# GPS.net
KiCad netlist of a schematic drawn in EAGLE
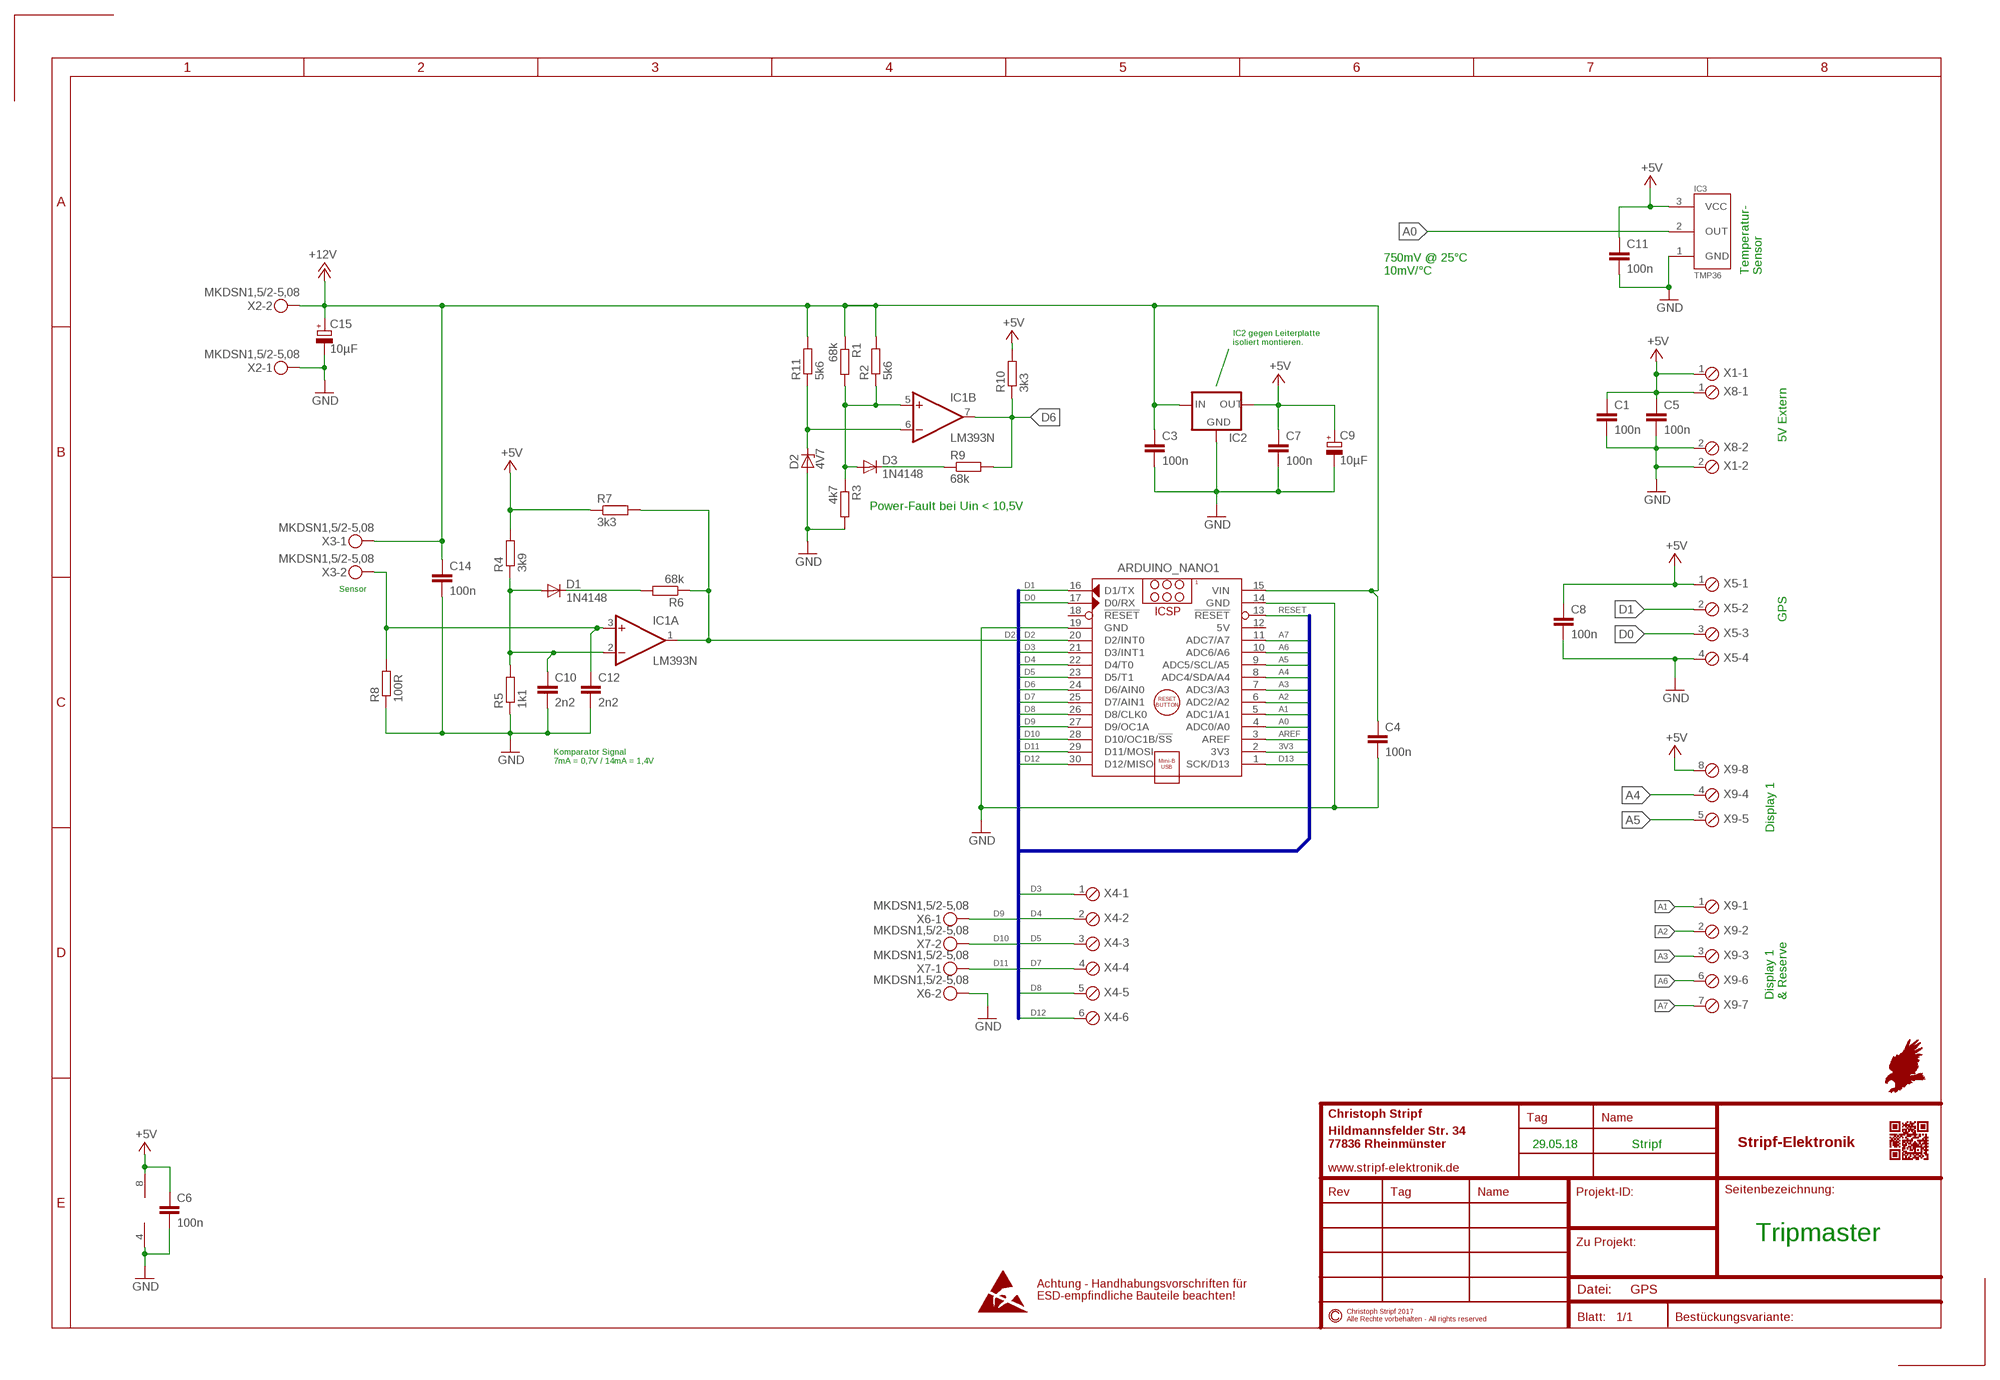
[diagram p0: schematic, sheet 1]

(export (version "E")
  (design (tool "Eeschema 10.0.6"))
  (components
    (comp (ref "ARDUINO_NANO1")
      (value "ARDUINO_NANO")
      (footprint "eagle-import:ARDUINO_NANO")
      (libsource (lib "eagle-import") (part "ARDUINO_NANO"))
    )
    (comp (ref "C1")
      (value "100n")
      (footprint "eagle-import:C025-030X050")
      (libsource (lib "eagle-import") (part "C-EU025-030X050"))
    )
    (comp (ref "C3")
      (value "100n")
      (footprint "eagle-import:C025-030X050")
      (libsource (lib "eagle-import") (part "C-EU025-030X050"))
    )
    (comp (ref "C4")
      (value "100n")
      (footprint "eagle-import:C025-030X050")
      (libsource (lib "eagle-import") (part "C-EU025-030X050"))
    )
    (comp (ref "C5")
      (value "100n")
      (footprint "eagle-import:C025-030X050")
      (libsource (lib "eagle-import") (part "C-EU025-030X050"))
    )
    (comp (ref "C6")
      (value "100n")
      (footprint "eagle-import:C025-030X050")
      (libsource (lib "eagle-import") (part "C-EU025-030X050"))
    )
    (comp (ref "C7")
      (value "100n")
      (footprint "eagle-import:C025-030X050")
      (libsource (lib "eagle-import") (part "C-EU025-030X050"))
    )
    (comp (ref "C8")
      (value "100n")
      (footprint "eagle-import:C025-030X050")
      (libsource (lib "eagle-import") (part "C-EU025-030X050"))
    )
    (comp (ref "C9")
      (value "10µF")
      (footprint "eagle-import:E2,5-6")
      (libsource (lib "eagle-import") (part "CPOL-EUE2.5-6"))
    )
    (comp (ref "C10")
      (value "2n2")
      (footprint "eagle-import:C025-030X050")
      (libsource (lib "eagle-import") (part "C-EU025-030X050"))
    )
    (comp (ref "C11")
      (value "100n")
      (footprint "eagle-import:C025-030X050")
      (libsource (lib "eagle-import") (part "C-EU025-030X050"))
    )
    (comp (ref "C12")
      (value "2n2")
      (footprint "eagle-import:C025-030X050")
      (libsource (lib "eagle-import") (part "C-EU025-030X050"))
    )
    (comp (ref "C14")
      (value "100n")
      (footprint "eagle-import:C025-030X050")
      (libsource (lib "eagle-import") (part "C-EU025-030X050"))
    )
    (comp (ref "C15")
      (value "10µF")
      (footprint "eagle-import:E2,5-6")
      (libsource (lib "eagle-import") (part "CPOL-EUE2.5-6"))
    )
    (comp (ref "D1")
      (value "1N4148")
      (footprint "eagle-import:DO35-7")
      (libsource (lib "eagle-import") (part "1N4148DO35-7"))
    )
    (comp (ref "D2")
      (value "4V7")
      (footprint "eagle-import:ZDIO-2.5")
      (libsource (lib "eagle-import") (part "ZENER-DIODEZD-2.5"))
    )
    (comp (ref "D3")
      (value "1N4148")
      (footprint "eagle-import:DO35-7")
      (libsource (lib "eagle-import") (part "1N4148DO35-7"))
    )
    (comp (ref "IC1")
      (value "LM393N")
      (footprint "eagle-import:DIL08")
      (libsource (lib "eagle-import") (part "LM393N"))
    )
    (comp (ref "IC2")
      (value "78XXL")
      (footprint "eagle-import:78XXL")
      (libsource (lib "eagle-import") (part "78XXL"))
    )
    (comp (ref "IC3")
      (value "TMP36")
      (footprint "eagle-import:TO92-LINE")
      (libsource (lib "eagle-import") (part "TMP36"))
    )
    (comp (ref "R1")
      (value "68k")
      (footprint "eagle-import:0207_2V")
      (libsource (lib "eagle-import") (part "R-EU_0207/2V"))
    )
    (comp (ref "R2")
      (value "5k6")
      (footprint "eagle-import:0207_2V")
      (libsource (lib "eagle-import") (part "R-EU_0207/2V"))
    )
    (comp (ref "R3")
      (value "4k7")
      (footprint "eagle-import:0207_2V")
      (libsource (lib "eagle-import") (part "R-EU_0207/2V"))
    )
    (comp (ref "R4")
      (value "3k9")
      (footprint "eagle-import:0207_2V")
      (libsource (lib "eagle-import") (part "R-EU_0207/2V"))
    )
    (comp (ref "R5")
      (value "1k1")
      (footprint "eagle-import:0207_2V")
      (libsource (lib "eagle-import") (part "R-EU_0207/2V"))
    )
    (comp (ref "R6")
      (value "68k")
      (footprint "eagle-import:0207_2V")
      (libsource (lib "eagle-import") (part "R-EU_0207/2V"))
    )
    (comp (ref "R7")
      (value "3k3")
      (footprint "eagle-import:0207_2V")
      (libsource (lib "eagle-import") (part "R-EU_0207/2V"))
    )
    (comp (ref "R8")
      (value "100R")
      (footprint "eagle-import:0207_2V")
      (libsource (lib "eagle-import") (part "R-EU_0207/2V"))
    )
    (comp (ref "R9")
      (value "68k")
      (footprint "eagle-import:0207_2V")
      (libsource (lib "eagle-import") (part "R-EU_0207/2V"))
    )
    (comp (ref "R10")
      (value "3k3")
      (footprint "eagle-import:0207_2V")
      (libsource (lib "eagle-import") (part "R-EU_0207/2V"))
    )
    (comp (ref "R11")
      (value "5k6")
      (footprint "eagle-import:0207_2V")
      (libsource (lib "eagle-import") (part "R-EU_0207/2V"))
    )
    (comp (ref "X1")
      (value "MPT2")
      (footprint "eagle-import:2POL254")
      (libsource (lib "eagle-import") (part "MPT2"))
    )
    (comp (ref "X2")
      (value "MKDSN1,5/2-5,08")
      (footprint "eagle-import:MKDSN1,5_2-5,08")
      (libsource (lib "eagle-import") (part "MKDSN1,5/2-5,08"))
    )
    (comp (ref "X3")
      (value "MKDSN1,5/2-5,08")
      (footprint "eagle-import:MKDSN1,5_2-5,08")
      (libsource (lib "eagle-import") (part "MKDSN1,5/2-5,08"))
    )
    (comp (ref "X4")
      (value "MPT6")
      (footprint "eagle-import:6POL254")
      (libsource (lib "eagle-import") (part "MPT6"))
    )
    (comp (ref "X5")
      (value "MPT4")
      (footprint "eagle-import:4POL254")
      (libsource (lib "eagle-import") (part "MPT4"))
    )
    (comp (ref "X6")
      (value "MKDSN1,5/2-5,08")
      (footprint "eagle-import:MKDSN1,5_2-5,08")
      (libsource (lib "eagle-import") (part "MKDSN1,5/2-5,08"))
    )
    (comp (ref "X7")
      (value "MKDSN1,5/2-5,08")
      (footprint "eagle-import:MKDSN1,5_2-5,08")
      (libsource (lib "eagle-import") (part "MKDSN1,5/2-5,08"))
    )
    (comp (ref "X8")
      (value "MPT2")
      (footprint "eagle-import:2POL254")
      (libsource (lib "eagle-import") (part "MPT2"))
    )
    (comp (ref "X9")
      (value "MPT8")
      (footprint "eagle-import:8POL254")
      (libsource (lib "eagle-import") (part "MPT8"))
    )
  )
  (nets
    (net (code "1") (name "+5V") (class "Default")
      (node (ref "C1") (pin "1") (pinfunction "1_1") (pintype "passive"))
      (node (ref "C11") (pin "1") (pinfunction "1_1") (pintype "passive"))
      (node (ref "C5") (pin "1") (pinfunction "1_1") (pintype "passive"))
      (node (ref "C6") (pin "1") (pinfunction "1_1") (pintype "passive"))
      (node (ref "C7") (pin "1") (pinfunction "1_1") (pintype "passive"))
      (node (ref "C8") (pin "1") (pinfunction "1_1") (pintype "passive"))
      (node (ref "C9") (pin "+") (pinfunction "+_+") (pintype "passive"))
      (node (ref "IC1") (pin "8") (pinfunction "V+_8") (pintype "power_in"))
      (node (ref "IC2") (pin "OUT") (pinfunction "OUT_OUT") (pintype "passive"))
      (node (ref "IC3") (pin "3") (pinfunction "VCC_3") (pintype "bidirectional"))
      (node (ref "R10") (pin "2") (pinfunction "2_2") (pintype "passive"))
      (node (ref "R4") (pin "2") (pinfunction "2_2") (pintype "passive"))
      (node (ref "R7") (pin "1") (pinfunction "1_1") (pintype "passive"))
      (node (ref "X1") (pin "1") (pinfunction "1_1") (pintype "passive"))
      (node (ref "X5") (pin "1") (pinfunction "1_1") (pintype "passive"))
      (node (ref "X8") (pin "1") (pinfunction "1_1") (pintype "passive"))
      (node (ref "X9") (pin "8") (pinfunction "1_8") (pintype "passive"))
    )
    (net (code "2") (name "+12V") (class "Default")
      (node (ref "ARDUINO_NANO1") (pin "15") (pinfunction "VIN_15") (pintype "power_in"))
      (node (ref "C14") (pin "1") (pinfunction "1_1") (pintype "passive"))
      (node (ref "C15") (pin "+") (pinfunction "+_+") (pintype "passive"))
      (node (ref "C3") (pin "1") (pinfunction "1_1") (pintype "passive"))
      (node (ref "C4") (pin "1") (pinfunction "1_1") (pintype "passive"))
      (node (ref "IC2") (pin "IN") (pinfunction "IN_IN") (pintype "input"))
      (node (ref "R1") (pin "1") (pinfunction "1_1") (pintype "passive"))
      (node (ref "R11") (pin "2") (pinfunction "2_2") (pintype "passive"))
      (node (ref "R2") (pin "2") (pinfunction "2_2") (pintype "passive"))
      (node (ref "X2") (pin "2") (pinfunction "KL_2") (pintype "passive"))
      (node (ref "X3") (pin "1") (pinfunction "KL_1") (pintype "passive"))
    )
    (net (code "3") (name "/3V3") (class "Default")
      (node (ref "ARDUINO_NANO1") (pin "2") (pinfunction "3V3_2") (pintype "output"))
    )
    (net (code "4") (name "/5V") (class "Default")
      (node (ref "ARDUINO_NANO1") (pin "12") (pinfunction "5V_12") (pintype "power_in"))
    )
    (net (code "5") (name "/AREF") (class "Default")
      (node (ref "ARDUINO_NANO1") (pin "3") (pinfunction "AREF_3") (pintype "input"))
    )
    (net (code "6") (name "/D2") (class "Default")
      (node (ref "ARDUINO_NANO1") (pin "20") (pinfunction "D2/INT0_20") (pintype "bidirectional"))
      (node (ref "IC1") (pin "1") (pinfunction "OUT_1") (pintype "output"))
      (node (ref "R6") (pin "1") (pinfunction "1_1") (pintype "passive"))
      (node (ref "R7") (pin "2") (pinfunction "2_2") (pintype "passive"))
    )
    (net (code "7") (name "/D3") (class "Default")
      (node (ref "ARDUINO_NANO1") (pin "21") (pinfunction "D3/INT1_21") (pintype "bidirectional"))
      (node (ref "X4") (pin "1") (pinfunction "1_1") (pintype "passive"))
    )
    (net (code "8") (name "/D4") (class "Default")
      (node (ref "ARDUINO_NANO1") (pin "22") (pinfunction "D4/T0_22") (pintype "bidirectional"))
      (node (ref "X4") (pin "2") (pinfunction "1_2") (pintype "passive"))
    )
    (net (code "9") (name "/D5") (class "Default")
      (node (ref "ARDUINO_NANO1") (pin "23") (pinfunction "D5/T1_23") (pintype "bidirectional"))
      (node (ref "X4") (pin "3") (pinfunction "1_3") (pintype "passive"))
    )
    (net (code "10") (name "/D7") (class "Default")
      (node (ref "ARDUINO_NANO1") (pin "25") (pinfunction "D7/AIN1_25") (pintype "bidirectional"))
      (node (ref "X4") (pin "4") (pinfunction "1_4") (pintype "passive"))
    )
    (net (code "11") (name "/D8") (class "Default")
      (node (ref "ARDUINO_NANO1") (pin "26") (pinfunction "D8/CLK0_26") (pintype "bidirectional"))
      (node (ref "X4") (pin "5") (pinfunction "1_5") (pintype "passive"))
    )
    (net (code "12") (name "/D9") (class "Default")
      (node (ref "ARDUINO_NANO1") (pin "27") (pinfunction "D9/OC1A_27") (pintype "bidirectional"))
      (node (ref "X6") (pin "1") (pinfunction "KL_1") (pintype "passive"))
    )
    (net (code "13") (name "/D10") (class "Default")
      (node (ref "ARDUINO_NANO1") (pin "28") (pinfunction "D10/OC1B/~{SS}_28") (pintype "bidirectional"))
      (node (ref "X7") (pin "2") (pinfunction "KL_2") (pintype "passive"))
    )
    (net (code "14") (name "/D11") (class "Default")
      (node (ref "ARDUINO_NANO1") (pin "29") (pinfunction "D11/MOSI_29") (pintype "bidirectional"))
      (node (ref "X7") (pin "1") (pinfunction "KL_1") (pintype "passive"))
    )
    (net (code "15") (name "/D12") (class "Default")
      (node (ref "ARDUINO_NANO1") (pin "30") (pinfunction "D12/MISO_30") (pintype "bidirectional"))
      (node (ref "X4") (pin "6") (pinfunction "1_6") (pintype "passive"))
    )
    (net (code "16") (name "/D13") (class "Default")
      (node (ref "ARDUINO_NANO1") (pin "1") (pinfunction "SCK/D13_1") (pintype "bidirectional"))
    )
    (net (code "17") (name "/RESET") (class "Default")
      (node (ref "ARDUINO_NANO1") (pin "13") (pinfunction "~{RESET}_13") (pintype "input"))
    )
    (net (code "18") (name "A0") (class "Default")
      (node (ref "ARDUINO_NANO1") (pin "4") (pinfunction "ADC0/A0_4") (pintype "bidirectional"))
      (node (ref "IC3") (pin "2") (pinfunction "OUT_2") (pintype "bidirectional"))
    )
    (net (code "19") (name "A1") (class "Default")
      (node (ref "ARDUINO_NANO1") (pin "5") (pinfunction "ADC1/A1_5") (pintype "bidirectional"))
      (node (ref "X9") (pin "1") (pinfunction "1_1") (pintype "passive"))
    )
    (net (code "20") (name "A2") (class "Default")
      (node (ref "ARDUINO_NANO1") (pin "6") (pinfunction "ADC2/A2_6") (pintype "bidirectional"))
      (node (ref "X9") (pin "2") (pinfunction "1_2") (pintype "passive"))
    )
    (net (code "21") (name "A3") (class "Default")
      (node (ref "ARDUINO_NANO1") (pin "7") (pinfunction "ADC3/A3_7") (pintype "bidirectional"))
      (node (ref "X9") (pin "3") (pinfunction "1_3") (pintype "passive"))
    )
    (net (code "22") (name "A4") (class "Default")
      (node (ref "ARDUINO_NANO1") (pin "8") (pinfunction "ADC4/SDA/A4_8") (pintype "bidirectional"))
      (node (ref "X9") (pin "4") (pinfunction "1_4") (pintype "passive"))
    )
    (net (code "23") (name "A5") (class "Default")
      (node (ref "ARDUINO_NANO1") (pin "9") (pinfunction "ADC5/SCL/A5_9") (pintype "bidirectional"))
      (node (ref "X9") (pin "5") (pinfunction "1_5") (pintype "passive"))
    )
    (net (code "24") (name "A6") (class "Default")
      (node (ref "ARDUINO_NANO1") (pin "10") (pinfunction "ADC6/A6_10") (pintype "bidirectional"))
      (node (ref "X9") (pin "6") (pinfunction "1_6") (pintype "passive"))
    )
    (net (code "25") (name "A7") (class "Default")
      (node (ref "ARDUINO_NANO1") (pin "11") (pinfunction "ADC7/A7_11") (pintype "bidirectional"))
      (node (ref "X9") (pin "7") (pinfunction "1_7") (pintype "passive"))
    )
    (net (code "26") (name "D0") (class "Default")
      (node (ref "ARDUINO_NANO1") (pin "17") (pinfunction "D0/RX_17") (pintype "bidirectional"))
      (node (ref "X5") (pin "3") (pinfunction "1_3") (pintype "passive"))
    )
    (net (code "27") (name "D1") (class "Default")
      (node (ref "ARDUINO_NANO1") (pin "16") (pinfunction "D1/TX_16") (pintype "bidirectional"))
      (node (ref "X5") (pin "2") (pinfunction "1_2") (pintype "passive"))
    )
    (net (code "28") (name "D6") (class "Default")
      (node (ref "ARDUINO_NANO1") (pin "24") (pinfunction "D6/AIN0_24") (pintype "bidirectional"))
      (node (ref "IC1") (pin "7") (pinfunction "OUT_7") (pintype "output"))
      (node (ref "R10") (pin "1") (pinfunction "1_1") (pintype "passive"))
      (node (ref "R9") (pin "2") (pinfunction "2_2") (pintype "passive"))
    )
    (net (code "29") (name "GND") (class "Default")
      (node (ref "ARDUINO_NANO1") (pin "14") (pinfunction "GND_14") (pintype "power_in"))
      (node (ref "ARDUINO_NANO1") (pin "19") (pinfunction "GND_19") (pintype "power_in"))
      (node (ref "C1") (pin "2") (pinfunction "2_2") (pintype "passive"))
      (node (ref "C10") (pin "2") (pinfunction "2_2") (pintype "passive"))
      (node (ref "C11") (pin "2") (pinfunction "2_2") (pintype "passive"))
      (node (ref "C12") (pin "2") (pinfunction "2_2") (pintype "passive"))
      (node (ref "C14") (pin "2") (pinfunction "2_2") (pintype "passive"))
      (node (ref "C15") (pin "-") (pinfunction "-_-") (pintype "passive"))
      (node (ref "C3") (pin "2") (pinfunction "2_2") (pintype "passive"))
      (node (ref "C4") (pin "2") (pinfunction "2_2") (pintype "passive"))
      (node (ref "C5") (pin "2") (pinfunction "2_2") (pintype "passive"))
      (node (ref "C6") (pin "2") (pinfunction "2_2") (pintype "passive"))
      (node (ref "C7") (pin "2") (pinfunction "2_2") (pintype "passive"))
      (node (ref "C8") (pin "2") (pinfunction "2_2") (pintype "passive"))
      (node (ref "C9") (pin "-") (pinfunction "-_-") (pintype "passive"))
      (node (ref "D2") (pin "A") (pinfunction "A_A") (pintype "passive"))
      (node (ref "IC1") (pin "4") (pinfunction "V-_4") (pintype "power_in"))
      (node (ref "IC2") (pin "GND") (pinfunction "GND_GND") (pintype "input"))
      (node (ref "IC3") (pin "1") (pinfunction "GND_1") (pintype "bidirectional"))
      (node (ref "R3") (pin "2") (pinfunction "2_2") (pintype "passive"))
      (node (ref "R5") (pin "1") (pinfunction "1_1") (pintype "passive"))
      (node (ref "R8") (pin "1") (pinfunction "1_1") (pintype "passive"))
      (node (ref "X1") (pin "2") (pinfunction "1_2") (pintype "passive"))
      (node (ref "X2") (pin "1") (pinfunction "KL_1") (pintype "passive"))
      (node (ref "X5") (pin "4") (pinfunction "1_4") (pintype "passive"))
      (node (ref "X6") (pin "2") (pinfunction "KL_2") (pintype "passive"))
      (node (ref "X8") (pin "2") (pinfunction "1_2") (pintype "passive"))
    )
    (net (code "30") (name "Net-(D1-PadC)") (class "Default")
      (node (ref "D1") (pin "C") (pinfunction "C_C") (pintype "passive"))
      (node (ref "R6") (pin "2") (pinfunction "2_2") (pintype "passive"))
    )
    (net (code "31") (name "Net-(D3-PadC)") (class "Default")
      (node (ref "D3") (pin "C") (pinfunction "C_C") (pintype "passive"))
      (node (ref "R9") (pin "1") (pinfunction "1_1") (pintype "passive"))
    )
    (net (code "32") (name "Net-(IC1A-+IN)") (class "Default")
      (node (ref "C12") (pin "1") (pinfunction "1_1") (pintype "passive"))
      (node (ref "IC1") (pin "3") (pinfunction "+IN_3") (pintype "input"))
      (node (ref "R8") (pin "2") (pinfunction "2_2") (pintype "passive"))
      (node (ref "X3") (pin "2") (pinfunction "KL_2") (pintype "passive"))
    )
    (net (code "33") (name "Net-(IC1A--IN)") (class "Default")
      (node (ref "C10") (pin "1") (pinfunction "1_1") (pintype "passive"))
      (node (ref "D1") (pin "A") (pinfunction "A_A") (pintype "passive"))
      (node (ref "IC1") (pin "2") (pinfunction "-IN_2") (pintype "input"))
      (node (ref "R4") (pin "1") (pinfunction "1_1") (pintype "passive"))
      (node (ref "R5") (pin "2") (pinfunction "2_2") (pintype "passive"))
    )
    (net (code "34") (name "Net-(IC1B-+IN)") (class "Default")
      (node (ref "D3") (pin "A") (pinfunction "A_A") (pintype "passive"))
      (node (ref "IC1") (pin "5") (pinfunction "+IN_5") (pintype "input"))
      (node (ref "R1") (pin "2") (pinfunction "2_2") (pintype "passive"))
      (node (ref "R2") (pin "1") (pinfunction "1_1") (pintype "passive"))
      (node (ref "R3") (pin "1") (pinfunction "1_1") (pintype "passive"))
    )
    (net (code "35") (name "Net-(IC1B--IN)") (class "Default")
      (node (ref "D2") (pin "C") (pinfunction "C_C") (pintype "passive"))
      (node (ref "IC1") (pin "6") (pinfunction "-IN_6") (pintype "input"))
      (node (ref "R11") (pin "1") (pinfunction "1_1") (pintype "passive"))
    )
    (net (code "36") (name "unconnected-(ARDUINO_NANO1-~{RESET}-Pad18)") (class "Default")
      (node (ref "ARDUINO_NANO1") (pin "18") (pinfunction "~{RESET}_18") (pintype "input"))
    )
  )
)
